# BOC_RS232.net
KiCad netlist of a schematic drawn in Altium Designer
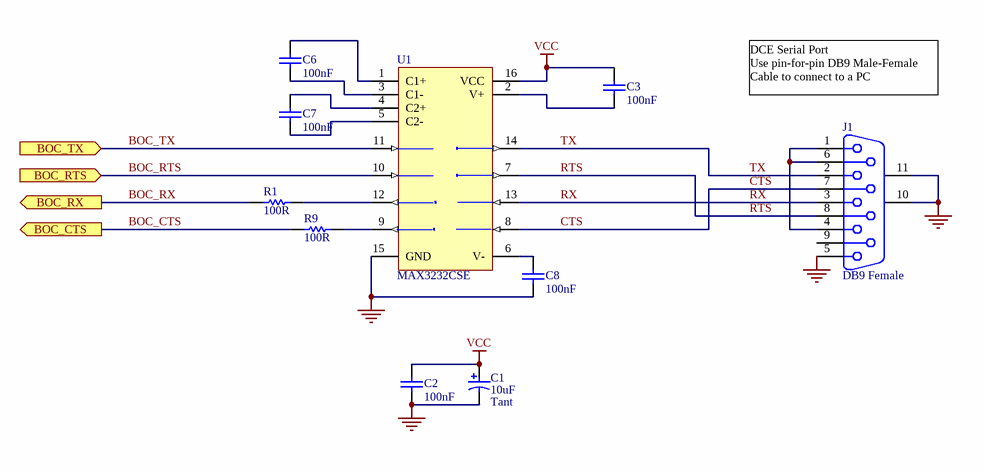
[diagram p0: BOC_RS232.SchDoc]

(export (version "E")
  (design (tool "Eeschema 10.0.6"))
  (components
    (comp (ref "C1")
      (value "10uF")
      (footprint "Altium Nanoboard Project:MCCT-B")
      (description "Polar Capacitor")
      (fields (field (name "CAPACITOR TYPE") "Tant"))
      (libsource (lib "Altium Nanoboard Project") (part "CAP_POLAR"))
    )
    (comp (ref "C2")
      (value "100nF")
      (footprint "Altium Nanoboard Project:CC2012-0805")
      (description "Capacitor")
      (libsource (lib "Altium Nanoboard Project") (part "CAP"))
    )
    (comp (ref "C3")
      (value "100nF")
      (footprint "Altium Nanoboard Project:CC2012-0805")
      (description "Capacitor")
      (libsource (lib "Altium Nanoboard Project") (part "CAP"))
    )
    (comp (ref "C6")
      (value "100nF")
      (footprint "Altium Nanoboard Project:CC2012-0805")
      (description "Capacitor")
      (libsource (lib "Altium Nanoboard Project") (part "CAP"))
    )
    (comp (ref "C7")
      (value "100nF")
      (footprint "Altium Nanoboard Project:CC2012-0805")
      (description "Capacitor")
      (libsource (lib "Altium Nanoboard Project") (part "CAP"))
    )
    (comp (ref "C8")
      (value "100nF")
      (footprint "Altium Nanoboard Project:CC2012-0805")
      (description "Capacitor")
      (libsource (lib "Altium Nanoboard Project") (part "CAP"))
    )
    (comp (ref "J1")
      (value "DB9 Female")
      (footprint "Altium Nanoboard Project:DSUB1.385-2H9")
      (description "Receptacle Assembly, 9 Position, Right Angle")
      (fields (field (name "MANUFACTURER") "Generic Components") (field (name "PUBLISHER") "Altium Limited"))
      (libsource (lib "Altium Nanoboard Project") (part "D Connector 9"))
    )
    (comp (ref "R1")
      (value "100R")
      (footprint "Altium Nanoboard Project:CC2012-0805")
      (description "Resistor")
      (libsource (lib "Altium Nanoboard Project") (part "RES"))
    )
    (comp (ref "R9")
      (value "100R")
      (footprint "Altium Nanoboard Project:CC2012-0805")
      (description "Resistor")
      (libsource (lib "Altium Nanoboard Project") (part "RES"))
    )
    (comp (ref "U1")
      (value "MAX3232CSE")
      (footprint "Altium Nanoboard Project:SO-G16")
      (description "3.0V TO 5.5V, Low-Power, up to 1Mbps, True RS-232 Transceiver Using Four 0.1µF External Capacitor")
      (fields (field (name "MANUFACTURER") "Maxim,ST") (field (name "PUBLISHER") "Altium Limited"))
      (libsource (lib "Altium Nanoboard Project") (part "MAX3232EUE"))
    )
  )
  (nets
    (net (code "1") (name "/BOC_CTS") (class "Default")
      (node (ref "R9") (pin "1") (pinfunction "1_1") (pintype "passive"))
    )
    (net (code "2") (name "/BOC_RTS") (class "Default")
      (node (ref "U1") (pin "10") (pinfunction "T2IN_10") (pintype "input"))
    )
    (net (code "3") (name "/BOC_RX") (class "Default")
      (node (ref "R1") (pin "1") (pinfunction "1_1") (pintype "passive"))
    )
    (net (code "4") (name "/BOC_TX") (class "Default")
      (node (ref "U1") (pin "11") (pinfunction "T1IN_11") (pintype "input"))
    )
    (net (code "5") (name "/CTS") (class "Default")
      (node (ref "J1") (pin "7") (pinfunction "7_7") (pintype "passive"))
      (node (ref "U1") (pin "8") (pinfunction "R2IN_8") (pintype "input"))
    )
    (net (code "6") (name "/RTS") (class "Default")
      (node (ref "J1") (pin "8") (pinfunction "8_8") (pintype "passive"))
      (node (ref "U1") (pin "7") (pinfunction "T2OUT_7") (pintype "output"))
    )
    (net (code "7") (name "/RX") (class "Default")
      (node (ref "J1") (pin "3") (pinfunction "3_3") (pintype "passive"))
      (node (ref "U1") (pin "13") (pinfunction "R1IN_13") (pintype "input"))
    )
    (net (code "8") (name "/TX") (class "Default")
      (node (ref "J1") (pin "2") (pinfunction "2_2") (pintype "passive"))
      (node (ref "U1") (pin "14") (pinfunction "T1OUT_14") (pintype "output"))
    )
    (net (code "9") (name "GND") (class "Default")
      (node (ref "C1") (pin "2") (pinfunction "2_2") (pintype "passive"))
      (node (ref "C2") (pin "2") (pinfunction "2_2") (pintype "passive"))
      (node (ref "C8") (pin "2") (pinfunction "2_2") (pintype "passive"))
      (node (ref "J1") (pin "10") (pinfunction "MH1_10") (pintype "passive"))
      (node (ref "J1") (pin "11") (pinfunction "MH2_11") (pintype "passive"))
      (node (ref "J1") (pin "5") (pinfunction "5_5") (pintype "passive"))
      (node (ref "U1") (pin "15") (pinfunction "GND_15") (pintype "power_in"))
    )
    (net (code "10") (name "Net-(J1-Pad1)") (class "Default")
      (node (ref "J1") (pin "1") (pinfunction "1_1") (pintype "passive"))
      (node (ref "J1") (pin "4") (pinfunction "4_4") (pintype "passive"))
      (node (ref "J1") (pin "6") (pinfunction "6_6") (pintype "passive"))
    )
    (net (code "11") (name "Net-(U1-C1+)") (class "Default")
      (node (ref "C6") (pin "1") (pinfunction "1_1") (pintype "passive"))
      (node (ref "U1") (pin "1") (pinfunction "C1+_1") (pintype "passive"))
    )
    (net (code "12") (name "Net-(U1-C1-)") (class "Default")
      (node (ref "C6") (pin "2") (pinfunction "2_2") (pintype "passive"))
      (node (ref "U1") (pin "3") (pinfunction "C1-_3") (pintype "passive"))
    )
    (net (code "13") (name "Net-(U1-C2+)") (class "Default")
      (node (ref "C7") (pin "1") (pinfunction "1_1") (pintype "passive"))
      (node (ref "U1") (pin "4") (pinfunction "C2+_4") (pintype "passive"))
    )
    (net (code "14") (name "Net-(U1-C2-)") (class "Default")
      (node (ref "C7") (pin "2") (pinfunction "2_2") (pintype "passive"))
      (node (ref "U1") (pin "5") (pinfunction "C2-_5") (pintype "passive"))
    )
    (net (code "15") (name "Net-(U1-R1OUT)") (class "Default")
      (node (ref "R1") (pin "2") (pinfunction "2_2") (pintype "passive"))
      (node (ref "U1") (pin "12") (pinfunction "R1OUT_12") (pintype "output"))
    )
    (net (code "16") (name "Net-(U1-R2OUT)") (class "Default")
      (node (ref "R9") (pin "2") (pinfunction "2_2") (pintype "passive"))
      (node (ref "U1") (pin "9") (pinfunction "R2OUT_9") (pintype "output"))
    )
    (net (code "17") (name "Net-(U1-V+)") (class "Default")
      (node (ref "C3") (pin "2") (pinfunction "2_2") (pintype "passive"))
      (node (ref "U1") (pin "2") (pinfunction "V+_2") (pintype "power_in"))
    )
    (net (code "18") (name "Net-(U1-V-)") (class "Default")
      (node (ref "C8") (pin "1") (pinfunction "1_1") (pintype "passive"))
      (node (ref "U1") (pin "6") (pinfunction "V-_6") (pintype "power_in"))
    )
    (net (code "19") (name "VCC") (class "Default")
      (node (ref "C1") (pin "1") (pinfunction "1_1") (pintype "passive"))
      (node (ref "C2") (pin "1") (pinfunction "1_1") (pintype "passive"))
      (node (ref "C3") (pin "1") (pinfunction "1_1") (pintype "passive"))
      (node (ref "U1") (pin "16") (pinfunction "VCC_16") (pintype "power_in"))
    )
    (net (code "20") (name "unconnected-(J1-Pad9)") (class "Default")
      (node (ref "J1") (pin "9") (pinfunction "9_9") (pintype "passive"))
    )
  )
)
